# fre_oa.net
KiCad netlist of a schematic drawn in Altium Designer
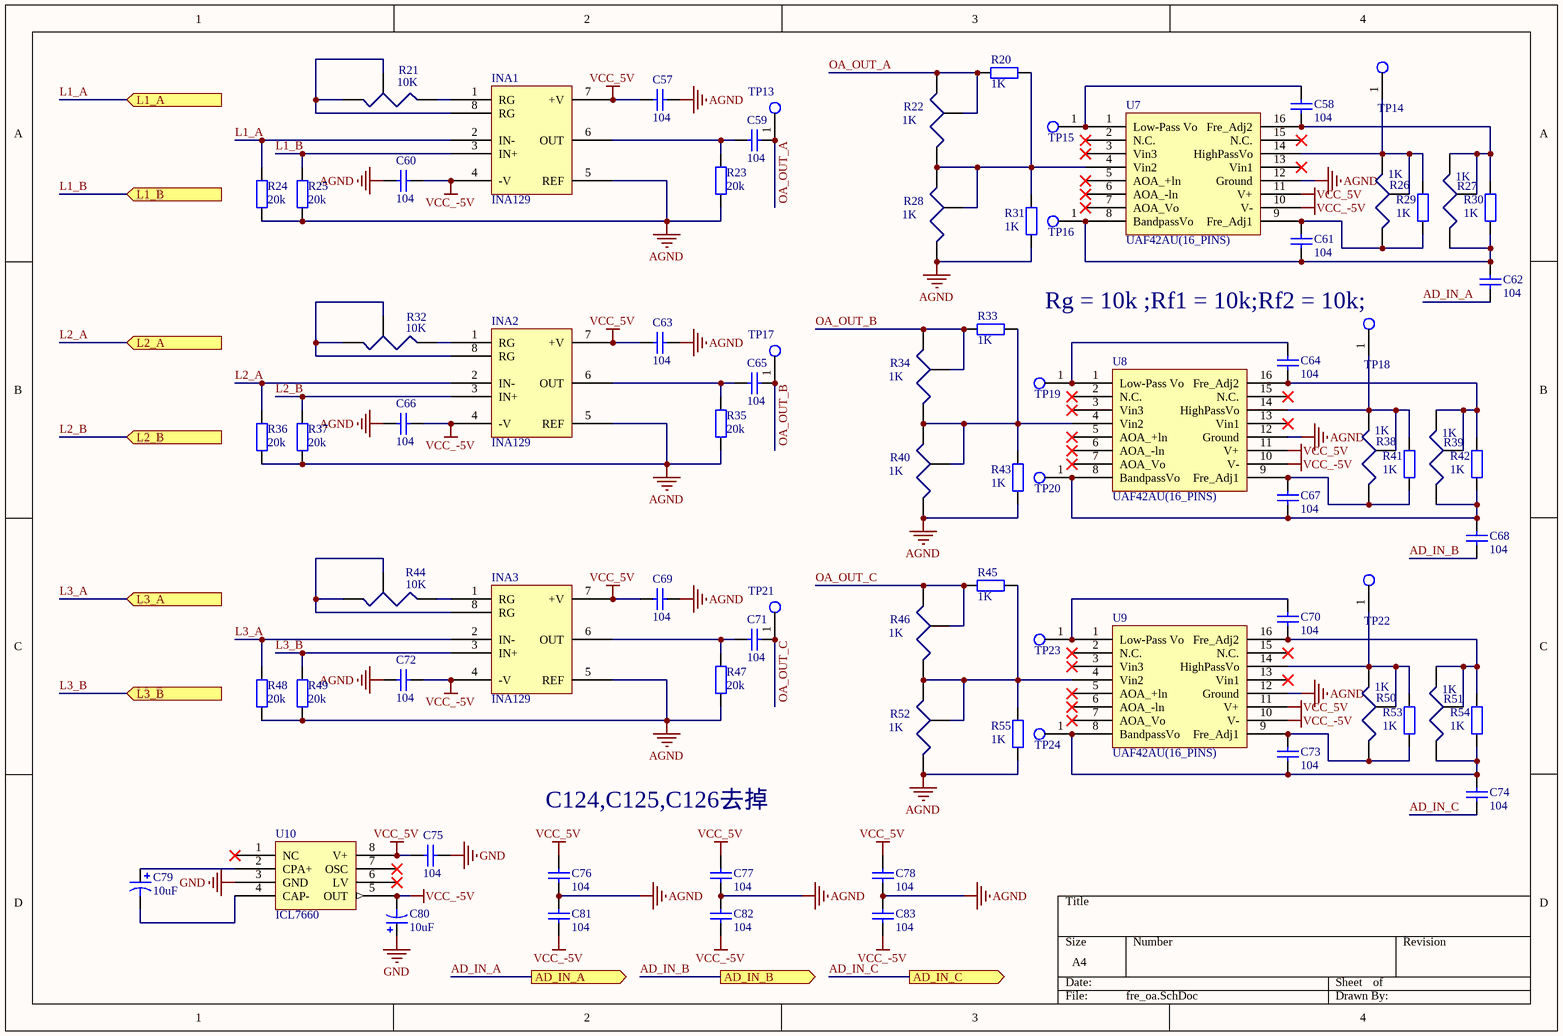
[diagram p0: fre_oa.SchDoc]

(export (version "E")
  (design (tool "Eeschema 10.0.6"))
  (components
    (comp (ref "C57")
      (value "104")
      (footprint "0805")
      (fields (field (name "Comment") "Cap"))
      (libsource (lib "自动化研究所集成库20170318") (part "Cap"))
    )
    (comp (ref "C58")
      (value "104")
      (footprint "0805")
      (fields (field (name "Comment") "Cap"))
      (libsource (lib "自动化研究所集成库20170318") (part "Cap"))
    )
    (comp (ref "C59")
      (value "104")
      (footprint "0805")
      (fields (field (name "Comment") "Cap"))
      (libsource (lib "自动化研究所集成库20170318") (part "Cap"))
    )
    (comp (ref "C60")
      (value "104")
      (footprint "0805")
      (fields (field (name "Comment") "Cap"))
      (libsource (lib "自动化研究所集成库20170318") (part "Cap"))
    )
    (comp (ref "C61")
      (value "104")
      (footprint "0805")
      (fields (field (name "Comment") "Cap"))
      (libsource (lib "自动化研究所集成库20170318") (part "Cap"))
    )
    (comp (ref "C62")
      (value "104")
      (footprint "0805")
      (fields (field (name "Comment") "Cap"))
      (libsource (lib "自动化研究所集成库20170318") (part "Cap"))
    )
    (comp (ref "C63")
      (value "104")
      (footprint "0805")
      (fields (field (name "Comment") "Cap"))
      (libsource (lib "自动化研究所集成库20170318") (part "Cap"))
    )
    (comp (ref "C64")
      (value "104")
      (footprint "0805")
      (fields (field (name "Comment") "Cap"))
      (libsource (lib "自动化研究所集成库20170318") (part "Cap"))
    )
    (comp (ref "C65")
      (value "104")
      (footprint "0805")
      (fields (field (name "Comment") "Cap"))
      (libsource (lib "自动化研究所集成库20170318") (part "Cap"))
    )
    (comp (ref "C66")
      (value "104")
      (footprint "0805")
      (fields (field (name "Comment") "Cap"))
      (libsource (lib "自动化研究所集成库20170318") (part "Cap"))
    )
    (comp (ref "C67")
      (value "104")
      (footprint "0805")
      (fields (field (name "Comment") "Cap"))
      (libsource (lib "自动化研究所集成库20170318") (part "Cap"))
    )
    (comp (ref "C68")
      (value "104")
      (footprint "0805")
      (fields (field (name "Comment") "Cap"))
      (libsource (lib "自动化研究所集成库20170318") (part "Cap"))
    )
    (comp (ref "C69")
      (value "104")
      (footprint "0805")
      (fields (field (name "Comment") "Cap"))
      (libsource (lib "自动化研究所集成库20170318") (part "Cap"))
    )
    (comp (ref "C70")
      (value "104")
      (footprint "0805")
      (fields (field (name "Comment") "Cap"))
      (libsource (lib "自动化研究所集成库20170318") (part "Cap"))
    )
    (comp (ref "C71")
      (value "104")
      (footprint "0805")
      (fields (field (name "Comment") "Cap"))
      (libsource (lib "自动化研究所集成库20170318") (part "Cap"))
    )
    (comp (ref "C72")
      (value "104")
      (footprint "0805")
      (fields (field (name "Comment") "Cap"))
      (libsource (lib "自动化研究所集成库20170318") (part "Cap"))
    )
    (comp (ref "C73")
      (value "104")
      (footprint "0805")
      (fields (field (name "Comment") "Cap"))
      (libsource (lib "自动化研究所集成库20170318") (part "Cap"))
    )
    (comp (ref "C74")
      (value "104")
      (footprint "0805")
      (fields (field (name "Comment") "Cap"))
      (libsource (lib "自动化研究所集成库20170318") (part "Cap"))
    )
    (comp (ref "C75")
      (value "104")
      (footprint "0805")
      (fields (field (name "Comment") "Cap"))
      (libsource (lib "自动化研究所集成库20170318") (part "Cap"))
    )
    (comp (ref "C76")
      (value "104")
      (footprint "0805")
      (fields (field (name "Comment") "Cap"))
      (libsource (lib "自动化研究所集成库20170318") (part "Cap"))
    )
    (comp (ref "C77")
      (value "104")
      (footprint "0805")
      (fields (field (name "Comment") "Cap"))
      (libsource (lib "自动化研究所集成库20170318") (part "Cap"))
    )
    (comp (ref "C78")
      (value "104")
      (footprint "0805")
      (fields (field (name "Comment") "Cap"))
      (libsource (lib "自动化研究所集成库20170318") (part "Cap"))
    )
    (comp (ref "C79")
      (value "10uF")
      (footprint "Cap 3528B")
      (fields (field (name "Comment") "Cap Poll"))
      (libsource (lib "自动化研究所集成库20170318") (part "Cap Poll"))
    )
    (comp (ref "C80")
      (value "10uF")
      (footprint "Cap 3528B")
      (fields (field (name "Comment") "Cap Poll"))
      (libsource (lib "自动化研究所集成库20170318") (part "Cap Poll"))
    )
    (comp (ref "C81")
      (value "104")
      (footprint "0805")
      (fields (field (name "Comment") "Cap"))
      (libsource (lib "自动化研究所集成库20170318") (part "Cap"))
    )
    (comp (ref "C82")
      (value "104")
      (footprint "0805")
      (fields (field (name "Comment") "Cap"))
      (libsource (lib "自动化研究所集成库20170318") (part "Cap"))
    )
    (comp (ref "C83")
      (value "104")
      (footprint "0805")
      (fields (field (name "Comment") "Cap"))
      (libsource (lib "自动化研究所集成库20170318") (part "Cap"))
    )
    (comp (ref "INA1")
      (value "INA129")
      (footprint "ElectromagneticPositioning1:LM386")
      (libsource (lib "Sensor") (part "INA129"))
    )
    (comp (ref "INA2")
      (value "INA129")
      (footprint "ElectromagneticPositioning1:LM386")
      (libsource (lib "Sensor") (part "INA129"))
    )
    (comp (ref "INA3")
      (value "INA129")
      (footprint "ElectromagneticPositioning1:LM386")
      (libsource (lib "Sensor") (part "INA129"))
    )
    (comp (ref "R20")
      (value "1K")
      (footprint "0805")
      (fields (field (name "Comment") "Res"))
      (libsource (lib "") (part "Res_1"))
    )
    (comp (ref "R21")
      (value "10K")
      (footprint "电位器WH06-2C")
      (fields (field (name "Comment") "电位器"))
      (libsource (lib "自动化研究所集成库20170318") (part "电位器"))
    )
    (comp (ref "R22")
      (value "1K")
      (footprint "电位器WH06-2C")
      (fields (field (name "Comment") "电位器"))
      (libsource (lib "自动化研究所集成库20170318") (part "电位器"))
    )
    (comp (ref "R23")
      (value "20k")
      (footprint "0805")
      (fields (field (name "Comment") "Res"))
      (libsource (lib "自动化研究所集成库20170318") (part "Res"))
    )
    (comp (ref "R24")
      (value "20k")
      (footprint "0805")
      (fields (field (name "Comment") "Res"))
      (libsource (lib "自动化研究所集成库20170318") (part "Res"))
    )
    (comp (ref "R25")
      (value "20k")
      (footprint "0805")
      (fields (field (name "Comment") "Res"))
      (libsource (lib "自动化研究所集成库20170318") (part "Res"))
    )
    (comp (ref "R26")
      (value "1K")
      (footprint "电位器WH06-2C")
      (fields (field (name "Comment") "电位器"))
      (libsource (lib "自动化研究所集成库20170318") (part "电位器"))
    )
    (comp (ref "R27")
      (value "1K")
      (footprint "电位器WH06-2C")
      (fields (field (name "Comment") "电位器"))
      (libsource (lib "自动化研究所集成库20170318") (part "电位器"))
    )
    (comp (ref "R28")
      (value "1K")
      (footprint "电位器WH06-2C")
      (fields (field (name "Comment") "电位器"))
      (libsource (lib "自动化研究所集成库20170318") (part "电位器"))
    )
    (comp (ref "R29")
      (value "1K")
      (footprint "0805")
      (fields (field (name "Comment") "Res"))
      (libsource (lib "自动化研究所集成库20170318") (part "Res"))
    )
    (comp (ref "R30")
      (value "1K")
      (footprint "0805")
      (fields (field (name "Comment") "Res"))
      (libsource (lib "自动化研究所集成库20170318") (part "Res"))
    )
    (comp (ref "R31")
      (value "1K")
      (footprint "0805")
      (fields (field (name "Comment") "Res"))
      (libsource (lib "自动化研究所集成库20170318") (part "Res"))
    )
    (comp (ref "R32")
      (value "10K")
      (footprint "电位器WH06-2C")
      (fields (field (name "Comment") "电位器"))
      (libsource (lib "自动化研究所集成库20170318") (part "电位器"))
    )
    (comp (ref "R33")
      (value "1K")
      (footprint "0805")
      (fields (field (name "Comment") "Res"))
      (libsource (lib "") (part "Res_1"))
    )
    (comp (ref "R34")
      (value "1K")
      (footprint "电位器WH06-2C")
      (fields (field (name "Comment") "电位器"))
      (libsource (lib "自动化研究所集成库20170318") (part "电位器"))
    )
    (comp (ref "R35")
      (value "20k")
      (footprint "0805")
      (fields (field (name "Comment") "Res"))
      (libsource (lib "自动化研究所集成库20170318") (part "Res"))
    )
    (comp (ref "R36")
      (value "20k")
      (footprint "0805")
      (fields (field (name "Comment") "Res"))
      (libsource (lib "自动化研究所集成库20170318") (part "Res"))
    )
    (comp (ref "R37")
      (value "20k")
      (footprint "0805")
      (fields (field (name "Comment") "Res"))
      (libsource (lib "自动化研究所集成库20170318") (part "Res"))
    )
    (comp (ref "R38")
      (value "1K")
      (footprint "电位器WH06-2C")
      (fields (field (name "Comment") "电位器"))
      (libsource (lib "自动化研究所集成库20170318") (part "电位器"))
    )
    (comp (ref "R39")
      (value "1K")
      (footprint "电位器WH06-2C")
      (fields (field (name "Comment") "电位器"))
      (libsource (lib "自动化研究所集成库20170318") (part "电位器"))
    )
    (comp (ref "R40")
      (value "1K")
      (footprint "电位器WH06-2C")
      (fields (field (name "Comment") "电位器"))
      (libsource (lib "自动化研究所集成库20170318") (part "电位器"))
    )
    (comp (ref "R41")
      (value "1K")
      (footprint "0805")
      (fields (field (name "Comment") "Res"))
      (libsource (lib "自动化研究所集成库20170318") (part "Res"))
    )
    (comp (ref "R42")
      (value "1K")
      (footprint "0805")
      (fields (field (name "Comment") "Res"))
      (libsource (lib "自动化研究所集成库20170318") (part "Res"))
    )
    (comp (ref "R43")
      (value "1K")
      (footprint "0805")
      (fields (field (name "Comment") "Res"))
      (libsource (lib "自动化研究所集成库20170318") (part "Res"))
    )
    (comp (ref "R44")
      (value "10K")
      (footprint "电位器WH06-2C")
      (fields (field (name "Comment") "电位器"))
      (libsource (lib "自动化研究所集成库20170318") (part "电位器"))
    )
    (comp (ref "R45")
      (value "1K")
      (footprint "0805")
      (fields (field (name "Comment") "Res"))
      (libsource (lib "") (part "Res_1"))
    )
    (comp (ref "R46")
      (value "1K")
      (footprint "电位器WH06-2C")
      (fields (field (name "Comment") "电位器"))
      (libsource (lib "自动化研究所集成库20170318") (part "电位器"))
    )
    (comp (ref "R47")
      (value "20k")
      (footprint "0805")
      (fields (field (name "Comment") "Res"))
      (libsource (lib "自动化研究所集成库20170318") (part "Res"))
    )
    (comp (ref "R48")
      (value "20k")
      (footprint "0805")
      (fields (field (name "Comment") "Res"))
      (libsource (lib "自动化研究所集成库20170318") (part "Res"))
    )
    (comp (ref "R49")
      (value "20k")
      (footprint "0805")
      (fields (field (name "Comment") "Res"))
      (libsource (lib "自动化研究所集成库20170318") (part "Res"))
    )
    (comp (ref "R50")
      (value "1K")
      (footprint "电位器WH06-2C")
      (fields (field (name "Comment") "电位器"))
      (libsource (lib "自动化研究所集成库20170318") (part "电位器"))
    )
    (comp (ref "R51")
      (value "1K")
      (footprint "电位器WH06-2C")
      (fields (field (name "Comment") "电位器"))
      (libsource (lib "自动化研究所集成库20170318") (part "电位器"))
    )
    (comp (ref "R52")
      (value "1K")
      (footprint "电位器WH06-2C")
      (fields (field (name "Comment") "电位器"))
      (libsource (lib "自动化研究所集成库20170318") (part "电位器"))
    )
    (comp (ref "R53")
      (value "1K")
      (footprint "0805")
      (fields (field (name "Comment") "Res"))
      (libsource (lib "自动化研究所集成库20170318") (part "Res"))
    )
    (comp (ref "R54")
      (value "1K")
      (footprint "0805")
      (fields (field (name "Comment") "Res"))
      (libsource (lib "自动化研究所集成库20170318") (part "Res"))
    )
    (comp (ref "R55")
      (value "1K")
      (footprint "0805")
      (fields (field (name "Comment") "Res"))
      (libsource (lib "自动化研究所集成库20170318") (part "Res"))
    )
    (comp (ref "TP13") (value "testPoint") (footprint "TP_H") (libsource (lib "Spartan") (part "TP")))
    (comp (ref "TP14") (value "testPoint") (footprint "TP_H") (libsource (lib "Spartan") (part "TP")))
    (comp (ref "TP15") (value "testPoint") (footprint "TP_H") (libsource (lib "Spartan") (part "TP")))
    (comp (ref "TP16") (value "testPoint") (footprint "TP_H") (libsource (lib "Spartan") (part "TP")))
    (comp (ref "TP17") (value "testPoint") (footprint "TP_H") (libsource (lib "Spartan") (part "TP")))
    (comp (ref "TP18") (value "testPoint") (footprint "TP_H") (libsource (lib "Spartan") (part "TP")))
    (comp (ref "TP19") (value "testPoint") (footprint "TP_H") (libsource (lib "Spartan") (part "TP")))
    (comp (ref "TP20") (value "testPoint") (footprint "TP_H") (libsource (lib "Spartan") (part "TP")))
    (comp (ref "TP21") (value "testPoint") (footprint "TP_H") (libsource (lib "Spartan") (part "TP")))
    (comp (ref "TP22") (value "testPoint") (footprint "TP_H") (libsource (lib "Spartan") (part "TP")))
    (comp (ref "TP23") (value "testPoint") (footprint "TP_H") (libsource (lib "Spartan") (part "TP")))
    (comp (ref "TP24") (value "testPoint") (footprint "TP_H") (libsource (lib "Spartan") (part "TP")))
    (comp (ref "U7")
      (value "UAF42AU(16_PINS)")
      (footprint "SOIC127P1030X265-16N")
      (libsource (lib "Dugu") (part "UAF42AU(16_PINS)"))
    )
    (comp (ref "U8")
      (value "UAF42AU(16_PINS)")
      (footprint "SOIC127P1030X265-16N")
      (libsource (lib "Dugu") (part "UAF42AU(16_PINS)"))
    )
    (comp (ref "U9")
      (value "UAF42AU(16_PINS)")
      (footprint "SOIC127P1030X265-16N")
      (libsource (lib "Dugu") (part "UAF42AU(16_PINS)"))
    )
    (comp (ref "U10")
      (value "ICL7660")
      (footprint "ICL7660 sop-8")
      (libsource (lib "自动化研究所集成库20170318") (part "ICL7660"))
    )
  )
  (nets
    (net (code "1") (name "/AD_IN_A") (class "Default")
      (node (ref "C62") (pin "2") (pinfunction "2_2") (pintype "passive"))
    )
    (net (code "2") (name "/AD_IN_B") (class "Default")
      (node (ref "C68") (pin "2") (pinfunction "2_2") (pintype "passive"))
    )
    (net (code "3") (name "/AD_IN_C") (class "Default")
      (node (ref "C74") (pin "2") (pinfunction "2_2") (pintype "passive"))
    )
    (net (code "4") (name "/L1_A") (class "Default")
      (node (ref "INA1") (pin "2") (pinfunction "IN-_2") (pintype "passive"))
      (node (ref "R24") (pin "2") (pinfunction "2_2") (pintype "passive"))
    )
    (net (code "5") (name "/L1_B") (class "Default")
      (node (ref "INA1") (pin "3") (pinfunction "IN+_3") (pintype "passive"))
      (node (ref "R25") (pin "2") (pinfunction "2_2") (pintype "passive"))
    )
    (net (code "6") (name "/L2_A") (class "Default")
      (node (ref "INA2") (pin "2") (pinfunction "IN-_2") (pintype "passive"))
      (node (ref "R36") (pin "2") (pinfunction "2_2") (pintype "passive"))
    )
    (net (code "7") (name "/L2_B") (class "Default")
      (node (ref "INA2") (pin "3") (pinfunction "IN+_3") (pintype "passive"))
      (node (ref "R37") (pin "2") (pinfunction "2_2") (pintype "passive"))
    )
    (net (code "8") (name "/L3_A") (class "Default")
      (node (ref "INA3") (pin "2") (pinfunction "IN-_2") (pintype "passive"))
      (node (ref "R48") (pin "2") (pinfunction "2_2") (pintype "passive"))
    )
    (net (code "9") (name "/L3_B") (class "Default")
      (node (ref "INA3") (pin "3") (pinfunction "IN+_3") (pintype "passive"))
      (node (ref "R49") (pin "2") (pinfunction "2_2") (pintype "passive"))
    )
    (net (code "10") (name "/OA_OUT_A") (class "Default")
      (node (ref "C59") (pin "2") (pinfunction "2_2") (pintype "passive"))
      (node (ref "R20") (pin "1") (pinfunction "1_1") (pintype "passive"))
      (node (ref "R22") (pin "2") (pintype "passive"))
      (node (ref "R22") (pin "3") (pintype "passive"))
      (node (ref "TP13") (pin "1") (pinfunction "1_1") (pintype "passive"))
    )
    (net (code "11") (name "/OA_OUT_B") (class "Default")
      (node (ref "C65") (pin "2") (pinfunction "2_2") (pintype "passive"))
      (node (ref "R33") (pin "1") (pinfunction "1_1") (pintype "passive"))
      (node (ref "R34") (pin "2") (pintype "passive"))
      (node (ref "R34") (pin "3") (pintype "passive"))
      (node (ref "TP17") (pin "1") (pinfunction "1_1") (pintype "passive"))
    )
    (net (code "12") (name "/OA_OUT_C") (class "Default")
      (node (ref "C71") (pin "2") (pinfunction "2_2") (pintype "passive"))
      (node (ref "R45") (pin "1") (pinfunction "1_1") (pintype "passive"))
      (node (ref "R46") (pin "2") (pintype "passive"))
      (node (ref "R46") (pin "3") (pintype "passive"))
      (node (ref "TP21") (pin "1") (pinfunction "1_1") (pintype "passive"))
    )
    (net (code "13") (name "AGND") (class "Default")
      (node (ref "C57") (pin "2") (pinfunction "2_2") (pintype "passive"))
      (node (ref "C60") (pin "1") (pinfunction "1_1") (pintype "passive"))
      (node (ref "C63") (pin "2") (pinfunction "2_2") (pintype "passive"))
      (node (ref "C66") (pin "1") (pinfunction "1_1") (pintype "passive"))
      (node (ref "C69") (pin "2") (pinfunction "2_2") (pintype "passive"))
      (node (ref "C72") (pin "1") (pinfunction "1_1") (pintype "passive"))
      (node (ref "C76") (pin "1") (pinfunction "1_1") (pintype "passive"))
      (node (ref "C77") (pin "1") (pinfunction "1_1") (pintype "passive"))
      (node (ref "C78") (pin "1") (pinfunction "1_1") (pintype "passive"))
      (node (ref "C81") (pin "2") (pinfunction "2_2") (pintype "passive"))
      (node (ref "C82") (pin "2") (pinfunction "2_2") (pintype "passive"))
      (node (ref "C83") (pin "2") (pinfunction "2_2") (pintype "passive"))
      (node (ref "INA1") (pin "5") (pinfunction "REF_5") (pintype "passive"))
      (node (ref "INA2") (pin "5") (pinfunction "REF_5") (pintype "passive"))
      (node (ref "INA3") (pin "5") (pinfunction "REF_5") (pintype "passive"))
      (node (ref "R23") (pin "1") (pinfunction "1_1") (pintype "passive"))
      (node (ref "R24") (pin "1") (pinfunction "1_1") (pintype "passive"))
      (node (ref "R25") (pin "1") (pinfunction "1_1") (pintype "passive"))
      (node (ref "R28") (pin "1") (pintype "passive"))
      (node (ref "R31") (pin "1") (pinfunction "1_1") (pintype "passive"))
      (node (ref "R35") (pin "1") (pinfunction "1_1") (pintype "passive"))
      (node (ref "R36") (pin "1") (pinfunction "1_1") (pintype "passive"))
      (node (ref "R37") (pin "1") (pinfunction "1_1") (pintype "passive"))
      (node (ref "R40") (pin "1") (pintype "passive"))
      (node (ref "R43") (pin "1") (pinfunction "1_1") (pintype "passive"))
      (node (ref "R47") (pin "1") (pinfunction "1_1") (pintype "passive"))
      (node (ref "R48") (pin "1") (pinfunction "1_1") (pintype "passive"))
      (node (ref "R49") (pin "1") (pinfunction "1_1") (pintype "passive"))
      (node (ref "R52") (pin "1") (pintype "passive"))
      (node (ref "R55") (pin "1") (pinfunction "1_1") (pintype "passive"))
      (node (ref "U7") (pin "12") (pinfunction "Ground_12") (pintype "passive"))
      (node (ref "U8") (pin "12") (pinfunction "Ground_12") (pintype "passive"))
      (node (ref "U9") (pin "12") (pinfunction "Ground_12") (pintype "passive"))
    )
    (net (code "14") (name "GND") (class "Default")
      (node (ref "C75") (pin "2") (pinfunction "2_2") (pintype "passive"))
      (node (ref "C80") (pin "1") (pinfunction "1_1") (pintype "passive"))
      (node (ref "U10") (pin "3") (pinfunction "GND_3") (pintype "power_in"))
    )
    (net (code "15") (name "Net-(INA1-OUT)") (class "Default")
      (node (ref "C59") (pin "1") (pinfunction "1_1") (pintype "passive"))
      (node (ref "INA1") (pin "6") (pinfunction "OUT_6") (pintype "passive"))
      (node (ref "R23") (pin "2") (pinfunction "2_2") (pintype "passive"))
    )
    (net (code "16") (name "Net-(INA1-RG-Pad1)") (class "Default")
      (node (ref "INA1") (pin "1") (pinfunction "RG_1") (pintype "passive"))
      (node (ref "R21") (pin "1") (pintype "passive"))
    )
    (net (code "17") (name "Net-(INA1-RG-Pad8)") (class "Default")
      (node (ref "INA1") (pin "8") (pinfunction "RG_8") (pintype "passive"))
      (node (ref "R21") (pin "2") (pintype "passive"))
      (node (ref "R21") (pin "3") (pintype "passive"))
    )
    (net (code "18") (name "Net-(INA2-OUT)") (class "Default")
      (node (ref "C65") (pin "1") (pinfunction "1_1") (pintype "passive"))
      (node (ref "INA2") (pin "6") (pinfunction "OUT_6") (pintype "passive"))
      (node (ref "R35") (pin "2") (pinfunction "2_2") (pintype "passive"))
    )
    (net (code "19") (name "Net-(INA2-RG-Pad1)") (class "Default")
      (node (ref "INA2") (pin "1") (pinfunction "RG_1") (pintype "passive"))
      (node (ref "R32") (pin "1") (pintype "passive"))
    )
    (net (code "20") (name "Net-(INA2-RG-Pad8)") (class "Default")
      (node (ref "INA2") (pin "8") (pinfunction "RG_8") (pintype "passive"))
      (node (ref "R32") (pin "2") (pintype "passive"))
      (node (ref "R32") (pin "3") (pintype "passive"))
    )
    (net (code "21") (name "Net-(INA3-OUT)") (class "Default")
      (node (ref "C71") (pin "1") (pinfunction "1_1") (pintype "passive"))
      (node (ref "INA3") (pin "6") (pinfunction "OUT_6") (pintype "passive"))
      (node (ref "R47") (pin "2") (pinfunction "2_2") (pintype "passive"))
    )
    (net (code "22") (name "Net-(INA3-RG-Pad1)") (class "Default")
      (node (ref "INA3") (pin "1") (pinfunction "RG_1") (pintype "passive"))
      (node (ref "R44") (pin "1") (pintype "passive"))
    )
    (net (code "23") (name "Net-(INA3-RG-Pad8)") (class "Default")
      (node (ref "INA3") (pin "8") (pinfunction "RG_8") (pintype "passive"))
      (node (ref "R44") (pin "2") (pintype "passive"))
      (node (ref "R44") (pin "3") (pintype "passive"))
    )
    (net (code "24") (name "Net-(U7-BandpassVo)") (class "Default")
      (node (ref "C61") (pin "2") (pinfunction "2_2") (pintype "passive"))
      (node (ref "C62") (pin "1") (pinfunction "1_1") (pintype "passive"))
      (node (ref "R27") (pin "1") (pintype "passive"))
      (node (ref "R30") (pin "1") (pinfunction "1_1") (pintype "passive"))
      (node (ref "TP16") (pin "1") (pinfunction "1_1") (pintype "passive"))
      (node (ref "U7") (pin "8") (pinfunction "BandpassVo_8") (pintype "power_in"))
    )
    (net (code "25") (name "Net-(U7-Fre_Adj1)") (class "Default")
      (node (ref "C61") (pin "1") (pinfunction "1_1") (pintype "passive"))
      (node (ref "R26") (pin "1") (pintype "passive"))
      (node (ref "R29") (pin "1") (pinfunction "1_1") (pintype "passive"))
      (node (ref "U7") (pin "9") (pinfunction "Fre_Adj1_9") (pintype "passive"))
    )
    (net (code "26") (name "Net-(U7-Fre_Adj2)") (class "Default")
      (node (ref "C58") (pin "2") (pinfunction "2_2") (pintype "passive"))
      (node (ref "R27") (pin "2") (pintype "passive"))
      (node (ref "R27") (pin "3") (pintype "passive"))
      (node (ref "R30") (pin "2") (pinfunction "2_2") (pintype "passive"))
      (node (ref "U7") (pin "16") (pinfunction "Fre_Adj2_16") (pintype "power_in"))
    )
    (net (code "27") (name "Net-(U7-HighPassVo)") (class "Default")
      (node (ref "R26") (pin "2") (pintype "passive"))
      (node (ref "R26") (pin "3") (pintype "passive"))
      (node (ref "R29") (pin "2") (pinfunction "2_2") (pintype "passive"))
      (node (ref "TP14") (pin "1") (pinfunction "1_1") (pintype "passive"))
      (node (ref "U7") (pin "14") (pinfunction "HighPassVo_14") (pintype "passive"))
    )
    (net (code "28") (name "Net-(U7-Low-Pass_Vo)") (class "Default")
      (node (ref "C58") (pin "1") (pinfunction "1_1") (pintype "passive"))
      (node (ref "TP15") (pin "1") (pinfunction "1_1") (pintype "passive"))
      (node (ref "U7") (pin "1") (pinfunction "Low-Pass_Vo_1") (pintype "passive"))
    )
    (net (code "29") (name "Net-(U7-Vin2)") (class "Default")
      (node (ref "R20") (pin "2") (pinfunction "2_2") (pintype "passive"))
      (node (ref "R22") (pin "1") (pintype "passive"))
      (node (ref "R28") (pin "2") (pintype "passive"))
      (node (ref "R28") (pin "3") (pintype "passive"))
      (node (ref "R31") (pin "2") (pinfunction "2_2") (pintype "passive"))
      (node (ref "U7") (pin "4") (pinfunction "Vin2_4") (pintype "passive"))
    )
    (net (code "30") (name "Net-(U8-BandpassVo)") (class "Default")
      (node (ref "C67") (pin "2") (pinfunction "2_2") (pintype "passive"))
      (node (ref "C68") (pin "1") (pinfunction "1_1") (pintype "passive"))
      (node (ref "R39") (pin "1") (pintype "passive"))
      (node (ref "R42") (pin "1") (pinfunction "1_1") (pintype "passive"))
      (node (ref "TP20") (pin "1") (pinfunction "1_1") (pintype "passive"))
      (node (ref "U8") (pin "8") (pinfunction "BandpassVo_8") (pintype "power_in"))
    )
    (net (code "31") (name "Net-(U8-Fre_Adj1)") (class "Default")
      (node (ref "C67") (pin "1") (pinfunction "1_1") (pintype "passive"))
      (node (ref "R38") (pin "1") (pintype "passive"))
      (node (ref "R41") (pin "1") (pinfunction "1_1") (pintype "passive"))
      (node (ref "U8") (pin "9") (pinfunction "Fre_Adj1_9") (pintype "passive"))
    )
    (net (code "32") (name "Net-(U8-Fre_Adj2)") (class "Default")
      (node (ref "C64") (pin "2") (pinfunction "2_2") (pintype "passive"))
      (node (ref "R39") (pin "2") (pintype "passive"))
      (node (ref "R39") (pin "3") (pintype "passive"))
      (node (ref "R42") (pin "2") (pinfunction "2_2") (pintype "passive"))
      (node (ref "U8") (pin "16") (pinfunction "Fre_Adj2_16") (pintype "power_in"))
    )
    (net (code "33") (name "Net-(U8-HighPassVo)") (class "Default")
      (node (ref "R38") (pin "2") (pintype "passive"))
      (node (ref "R38") (pin "3") (pintype "passive"))
      (node (ref "R41") (pin "2") (pinfunction "2_2") (pintype "passive"))
      (node (ref "TP18") (pin "1") (pinfunction "1_1") (pintype "passive"))
      (node (ref "U8") (pin "14") (pinfunction "HighPassVo_14") (pintype "passive"))
    )
    (net (code "34") (name "Net-(U8-Low-Pass_Vo)") (class "Default")
      (node (ref "C64") (pin "1") (pinfunction "1_1") (pintype "passive"))
      (node (ref "TP19") (pin "1") (pinfunction "1_1") (pintype "passive"))
      (node (ref "U8") (pin "1") (pinfunction "Low-Pass_Vo_1") (pintype "passive"))
    )
    (net (code "35") (name "Net-(U8-Vin2)") (class "Default")
      (node (ref "R33") (pin "2") (pinfunction "2_2") (pintype "passive"))
      (node (ref "R34") (pin "1") (pintype "passive"))
      (node (ref "R40") (pin "2") (pintype "passive"))
      (node (ref "R40") (pin "3") (pintype "passive"))
      (node (ref "R43") (pin "2") (pinfunction "2_2") (pintype "passive"))
      (node (ref "U8") (pin "4") (pinfunction "Vin2_4") (pintype "passive"))
    )
    (net (code "36") (name "Net-(U9-BandpassVo)") (class "Default")
      (node (ref "C73") (pin "2") (pinfunction "2_2") (pintype "passive"))
      (node (ref "C74") (pin "1") (pinfunction "1_1") (pintype "passive"))
      (node (ref "R51") (pin "1") (pintype "passive"))
      (node (ref "R54") (pin "1") (pinfunction "1_1") (pintype "passive"))
      (node (ref "TP24") (pin "1") (pinfunction "1_1") (pintype "passive"))
      (node (ref "U9") (pin "8") (pinfunction "BandpassVo_8") (pintype "power_in"))
    )
    (net (code "37") (name "Net-(U9-Fre_Adj1)") (class "Default")
      (node (ref "C73") (pin "1") (pinfunction "1_1") (pintype "passive"))
      (node (ref "R50") (pin "1") (pintype "passive"))
      (node (ref "R53") (pin "1") (pinfunction "1_1") (pintype "passive"))
      (node (ref "U9") (pin "9") (pinfunction "Fre_Adj1_9") (pintype "passive"))
    )
    (net (code "38") (name "Net-(U9-Fre_Adj2)") (class "Default")
      (node (ref "C70") (pin "2") (pinfunction "2_2") (pintype "passive"))
      (node (ref "R51") (pin "2") (pintype "passive"))
      (node (ref "R51") (pin "3") (pintype "passive"))
      (node (ref "R54") (pin "2") (pinfunction "2_2") (pintype "passive"))
      (node (ref "U9") (pin "16") (pinfunction "Fre_Adj2_16") (pintype "power_in"))
    )
    (net (code "39") (name "Net-(U9-HighPassVo)") (class "Default")
      (node (ref "R50") (pin "2") (pintype "passive"))
      (node (ref "R50") (pin "3") (pintype "passive"))
      (node (ref "R53") (pin "2") (pinfunction "2_2") (pintype "passive"))
      (node (ref "TP22") (pin "1") (pinfunction "1_1") (pintype "passive"))
      (node (ref "U9") (pin "14") (pinfunction "HighPassVo_14") (pintype "passive"))
    )
    (net (code "40") (name "Net-(U9-Low-Pass_Vo)") (class "Default")
      (node (ref "C70") (pin "1") (pinfunction "1_1") (pintype "passive"))
      (node (ref "TP23") (pin "1") (pinfunction "1_1") (pintype "passive"))
      (node (ref "U9") (pin "1") (pinfunction "Low-Pass_Vo_1") (pintype "passive"))
    )
    (net (code "41") (name "Net-(U9-Vin2)") (class "Default")
      (node (ref "R45") (pin "2") (pinfunction "2_2") (pintype "passive"))
      (node (ref "R46") (pin "1") (pintype "passive"))
      (node (ref "R52") (pin "2") (pintype "passive"))
      (node (ref "R52") (pin "3") (pintype "passive"))
      (node (ref "R55") (pin "2") (pinfunction "2_2") (pintype "passive"))
      (node (ref "U9") (pin "4") (pinfunction "Vin2_4") (pintype "passive"))
    )
    (net (code "42") (name "Net-(U10-CAP-)") (class "Default")
      (node (ref "C79") (pin "2") (pinfunction "2_2") (pintype "passive"))
      (node (ref "U10") (pin "4") (pinfunction "CAP-_4") (pintype "passive"))
    )
    (net (code "43") (name "Net-(U10-CPA+)") (class "Default")
      (node (ref "C79") (pin "1") (pinfunction "1_1") (pintype "passive"))
      (node (ref "U10") (pin "2") (pinfunction "CPA+_2") (pintype "passive"))
    )
    (net (code "44") (name "VCC_-5V") (class "Default")
      (node (ref "C60") (pin "2") (pinfunction "2_2") (pintype "passive"))
      (node (ref "C66") (pin "2") (pinfunction "2_2") (pintype "passive"))
      (node (ref "C72") (pin "2") (pinfunction "2_2") (pintype "passive"))
      (node (ref "C80") (pin "2") (pinfunction "2_2") (pintype "passive"))
      (node (ref "C81") (pin "1") (pinfunction "1_1") (pintype "passive"))
      (node (ref "C82") (pin "1") (pinfunction "1_1") (pintype "passive"))
      (node (ref "C83") (pin "1") (pinfunction "1_1") (pintype "passive"))
      (node (ref "INA1") (pin "4") (pinfunction "-V_4") (pintype "passive"))
      (node (ref "INA2") (pin "4") (pinfunction "-V_4") (pintype "passive"))
      (node (ref "INA3") (pin "4") (pinfunction "-V_4") (pintype "passive"))
      (node (ref "U10") (pin "5") (pinfunction "OUT_5") (pintype "output"))
      (node (ref "U7") (pin "10") (pinfunction "V-_10") (pintype "passive"))
      (node (ref "U8") (pin "10") (pinfunction "V-_10") (pintype "passive"))
      (node (ref "U9") (pin "10") (pinfunction "V-_10") (pintype "passive"))
    )
    (net (code "45") (name "VCC_5V") (class "Default")
      (node (ref "C57") (pin "1") (pinfunction "1_1") (pintype "passive"))
      (node (ref "C63") (pin "1") (pinfunction "1_1") (pintype "passive"))
      (node (ref "C69") (pin "1") (pinfunction "1_1") (pintype "passive"))
      (node (ref "C75") (pin "1") (pinfunction "1_1") (pintype "passive"))
      (node (ref "C76") (pin "2") (pinfunction "2_2") (pintype "passive"))
      (node (ref "C77") (pin "2") (pinfunction "2_2") (pintype "passive"))
      (node (ref "C78") (pin "2") (pinfunction "2_2") (pintype "passive"))
      (node (ref "INA1") (pin "7") (pinfunction "+V_7") (pintype "passive"))
      (node (ref "INA2") (pin "7") (pinfunction "+V_7") (pintype "passive"))
      (node (ref "INA3") (pin "7") (pinfunction "+V_7") (pintype "passive"))
      (node (ref "U10") (pin "8") (pinfunction "V+_8") (pintype "power_in"))
      (node (ref "U7") (pin "11") (pinfunction "V+_11") (pintype "passive"))
      (node (ref "U8") (pin "11") (pinfunction "V+_11") (pintype "passive"))
      (node (ref "U9") (pin "11") (pinfunction "V+_11") (pintype "passive"))
    )
    (net (code "46") (name "unconnected-(U7-AOA_+ln-Pad5)") (class "Default")
      (node (ref "U7") (pin "5") (pinfunction "AOA_+ln_5") (pintype "passive+no_connect"))
    )
    (net (code "47") (name "unconnected-(U7-AOA_-ln-Pad6)") (class "Default")
      (node (ref "U7") (pin "6") (pinfunction "AOA_-ln_6") (pintype "passive+no_connect"))
    )
    (net (code "48") (name "unconnected-(U7-AOA_Vo-Pad7)") (class "Default")
      (node (ref "U7") (pin "7") (pinfunction "AOA_Vo_7") (pintype "passive+no_connect"))
    )
    (net (code "49") (name "unconnected-(U7-N.C.-Pad2)") (class "Default")
      (node (ref "U7") (pin "2") (pinfunction "N.C._2") (pintype "passive+no_connect"))
    )
    (net (code "50") (name "unconnected-(U7-N.C.-Pad15)") (class "Default")
      (node (ref "U7") (pin "15") (pinfunction "N.C._15") (pintype "passive+no_connect"))
    )
    (net (code "51") (name "unconnected-(U7-Vin1-Pad13)") (class "Default")
      (node (ref "U7") (pin "13") (pinfunction "Vin1_13") (pintype "passive+no_connect"))
    )
    (net (code "52") (name "unconnected-(U7-Vin3-Pad3)") (class "Default")
      (node (ref "U7") (pin "3") (pinfunction "Vin3_3") (pintype "passive+no_connect"))
    )
    (net (code "53") (name "unconnected-(U8-AOA_+ln-Pad5)") (class "Default")
      (node (ref "U8") (pin "5") (pinfunction "AOA_+ln_5") (pintype "passive+no_connect"))
    )
    (net (code "54") (name "unconnected-(U8-AOA_-ln-Pad6)") (class "Default")
      (node (ref "U8") (pin "6") (pinfunction "AOA_-ln_6") (pintype "passive+no_connect"))
    )
    (net (code "55") (name "unconnected-(U8-AOA_Vo-Pad7)") (class "Default")
      (node (ref "U8") (pin "7") (pinfunction "AOA_Vo_7") (pintype "passive+no_connect"))
    )
    (net (code "56") (name "unconnected-(U8-N.C.-Pad2)") (class "Default")
      (node (ref "U8") (pin "2") (pinfunction "N.C._2") (pintype "passive+no_connect"))
    )
    (net (code "57") (name "unconnected-(U8-N.C.-Pad15)") (class "Default")
      (node (ref "U8") (pin "15") (pinfunction "N.C._15") (pintype "passive+no_connect"))
    )
    (net (code "58") (name "unconnected-(U8-Vin1-Pad13)") (class "Default")
      (node (ref "U8") (pin "13") (pinfunction "Vin1_13") (pintype "passive+no_connect"))
    )
    (net (code "59") (name "unconnected-(U8-Vin3-Pad3)") (class "Default")
      (node (ref "U8") (pin "3") (pinfunction "Vin3_3") (pintype "passive+no_connect"))
    )
    (net (code "60") (name "unconnected-(U9-AOA_+ln-Pad5)") (class "Default")
      (node (ref "U9") (pin "5") (pinfunction "AOA_+ln_5") (pintype "passive+no_connect"))
    )
    (net (code "61") (name "unconnected-(U9-AOA_-ln-Pad6)") (class "Default")
      (node (ref "U9") (pin "6") (pinfunction "AOA_-ln_6") (pintype "passive+no_connect"))
    )
    (net (code "62") (name "unconnected-(U9-AOA_Vo-Pad7)") (class "Default")
      (node (ref "U9") (pin "7") (pinfunction "AOA_Vo_7") (pintype "passive+no_connect"))
    )
    (net (code "63") (name "unconnected-(U9-N.C.-Pad2)") (class "Default")
      (node (ref "U9") (pin "2") (pinfunction "N.C._2") (pintype "passive+no_connect"))
    )
    (net (code "64") (name "unconnected-(U9-N.C.-Pad15)") (class "Default")
      (node (ref "U9") (pin "15") (pinfunction "N.C._15") (pintype "passive+no_connect"))
    )
    (net (code "65") (name "unconnected-(U9-Vin1-Pad13)") (class "Default")
      (node (ref "U9") (pin "13") (pinfunction "Vin1_13") (pintype "passive+no_connect"))
    )
    (net (code "66") (name "unconnected-(U9-Vin3-Pad3)") (class "Default")
      (node (ref "U9") (pin "3") (pinfunction "Vin3_3") (pintype "passive+no_connect"))
    )
    (net (code "67") (name "unconnected-(U10-LV-Pad6)") (class "Default")
      (node (ref "U10") (pin "6") (pinfunction "LV_6") (pintype "passive+no_connect"))
    )
    (net (code "68") (name "unconnected-(U10-NC-Pad1)") (class "Default")
      (node (ref "U10") (pin "1") (pinfunction "NC_1") (pintype "passive+no_connect"))
    )
    (net (code "69") (name "unconnected-(U10-OSC-Pad7)") (class "Default")
      (node (ref "U10") (pin "7") (pinfunction "OSC_7") (pintype "passive+no_connect"))
    )
  )
)
